# connectors.net
KiCad netlist of a schematic drawn in Altium Designer
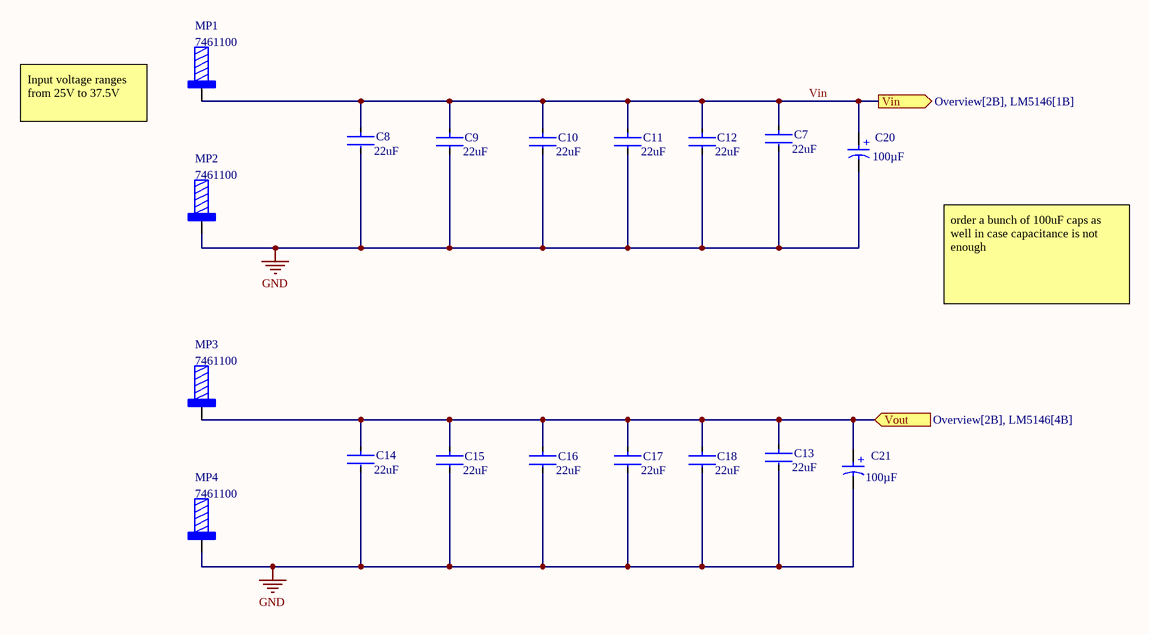
[diagram p0: connectors.SchDoc]

(export (version "E")
  (design (tool "Eeschema 10.0.6"))
  (components
    (comp (ref "C7")
      (value "C2220C226M5R2C7289")
      (footprint "FP-C2220C226M5R2C7289-MFG")
      (description "CAP CER 22UF 50V X7R SMD")
      (fields (field (name "TOLERANCE") "20%") (field (name "CAPACITANCE") "22uF"))
      (libsource (lib "Altium Content Vault") (part "02cd4be3c70576c341d710602a673aa"))
    )
    (comp (ref "C8")
      (value "C2220C226M5R2C7289")
      (footprint "FP-C2220C226M5R2C7289-MFG")
      (description "CAP CER 22UF 50V X7R SMD")
      (fields (field (name "TOLERANCE") "20%") (field (name "CAPACITANCE") "22uF"))
      (libsource (lib "Altium Content Vault") (part "02cd4be3c70576c341d710602a673aa"))
    )
    (comp (ref "C9")
      (value "C2220C226M5R2C7289")
      (footprint "FP-C2220C226M5R2C7289-MFG")
      (description "CAP CER 22UF 50V X7R SMD")
      (fields (field (name "TOLERANCE") "20%") (field (name "CAPACITANCE") "22uF"))
      (libsource (lib "Altium Content Vault") (part "02cd4be3c70576c341d710602a673aa"))
    )
    (comp (ref "C10")
      (value "C2220C226M5R2C7289")
      (footprint "FP-C2220C226M5R2C7289-MFG")
      (description "CAP CER 22UF 50V X7R SMD")
      (fields (field (name "TOLERANCE") "20%") (field (name "CAPACITANCE") "22uF"))
      (libsource (lib "Altium Content Vault") (part "02cd4be3c70576c341d710602a673aa"))
    )
    (comp (ref "C11")
      (value "C2220C226M5R2C7289")
      (footprint "FP-C2220C226M5R2C7289-MFG")
      (description "CAP CER 22UF 50V X7R SMD")
      (fields (field (name "TOLERANCE") "20%") (field (name "CAPACITANCE") "22uF"))
      (libsource (lib "Altium Content Vault") (part "02cd4be3c70576c341d710602a673aa"))
    )
    (comp (ref "C12")
      (value "C2220C226M5R2C7289")
      (footprint "FP-C2220C226M5R2C7289-MFG")
      (description "CAP CER 22UF 50V X7R SMD")
      (fields (field (name "TOLERANCE") "20%") (field (name "CAPACITANCE") "22uF"))
      (libsource (lib "Altium Content Vault") (part "02cd4be3c70576c341d710602a673aa"))
    )
    (comp (ref "C13")
      (value "C2220C226M5R2C7289")
      (footprint "FP-C2220C226M5R2C7289-MFG")
      (description "CAP CER 22UF 50V X7R SMD")
      (fields (field (name "TOLERANCE") "20%") (field (name "CAPACITANCE") "22uF"))
      (libsource (lib "Altium Content Vault") (part "02cd4be3c70576c341d710602a673aa"))
    )
    (comp (ref "C14")
      (value "C2220C226M5R2C7289")
      (footprint "FP-C2220C226M5R2C7289-MFG")
      (description "CAP CER 22UF 50V X7R SMD")
      (fields (field (name "TOLERANCE") "20%") (field (name "CAPACITANCE") "22uF"))
      (libsource (lib "Altium Content Vault") (part "02cd4be3c70576c341d710602a673aa"))
    )
    (comp (ref "C15")
      (value "C2220C226M5R2C7289")
      (footprint "FP-C2220C226M5R2C7289-MFG")
      (description "CAP CER 22UF 50V X7R SMD")
      (fields (field (name "TOLERANCE") "20%") (field (name "CAPACITANCE") "22uF"))
      (libsource (lib "Altium Content Vault") (part "02cd4be3c70576c341d710602a673aa"))
    )
    (comp (ref "C16")
      (value "C2220C226M5R2C7289")
      (footprint "FP-C2220C226M5R2C7289-MFG")
      (description "CAP CER 22UF 50V X7R SMD")
      (fields (field (name "TOLERANCE") "20%") (field (name "CAPACITANCE") "22uF"))
      (libsource (lib "Altium Content Vault") (part "02cd4be3c70576c341d710602a673aa"))
    )
    (comp (ref "C17")
      (value "C2220C226M5R2C7289")
      (footprint "FP-C2220C226M5R2C7289-MFG")
      (description "CAP CER 22UF 50V X7R SMD")
      (fields (field (name "TOLERANCE") "20%") (field (name "CAPACITANCE") "22uF"))
      (libsource (lib "Altium Content Vault") (part "02cd4be3c70576c341d710602a673aa"))
    )
    (comp (ref "C18")
      (value "C2220C226M5R2C7289")
      (footprint "FP-C2220C226M5R2C7289-MFG")
      (description "CAP CER 22UF 50V X7R SMD")
      (fields (field (name "TOLERANCE") "20%") (field (name "CAPACITANCE") "22uF"))
      (libsource (lib "Altium Content Vault") (part "02cd4be3c70576c341d710602a673aa"))
    )
    (comp (ref "C20")
      (value "860040674004")
      (footprint "WCAP-ATUL_D8H11.5")
      (description "WCAP-ATUL Aluminum Electrolytic Capacitors")
      (fields (field (name "TOLERANCE") "20%") (field (name "CAPACITANCE") "100µF"))
      (libsource (lib "Altium Content Vault") (part "Capacitor_Polarized"))
    )
    (comp (ref "C21")
      (value "860040674004")
      (footprint "WCAP-ATUL_D8H11.5")
      (description "WCAP-ATUL Aluminum Electrolytic Capacitors")
      (fields (field (name "TOLERANCE") "20%") (field (name "CAPACITANCE") "100µF"))
      (libsource (lib "Altium Content Vault") (part "Capacitor_Polarized"))
    )
    (comp (ref "MP1")
      (value "7461100")
      (footprint "7461100_chemical surface")
      (description "PCB power element shank terminal, 36P M10")
      (libsource (lib "Altium Content Vault") (part "WP-SHFU"))
    )
    (comp (ref "MP2")
      (value "7461100")
      (footprint "7461100_chemical surface")
      (description "PCB power element shank terminal, 36P M10")
      (libsource (lib "Altium Content Vault") (part "WP-SHFU"))
    )
    (comp (ref "MP3")
      (value "7461100")
      (footprint "7461100_chemical surface")
      (description "PCB power element shank terminal, 36P M10")
      (libsource (lib "Altium Content Vault") (part "WP-SHFU"))
    )
    (comp (ref "MP4")
      (value "7461100")
      (footprint "7461100_chemical surface")
      (description "PCB power element shank terminal, 36P M10")
      (libsource (lib "Altium Content Vault") (part "WP-SHFU"))
    )
  )
  (nets
    (net (code "1") (name "/Vin") (class "Default")
      (node (ref "C10") (pin "1") (pinfunction "1_1") (pintype "passive"))
      (node (ref "C11") (pin "1") (pinfunction "1_1") (pintype "passive"))
      (node (ref "C12") (pin "1") (pinfunction "1_1") (pintype "passive"))
      (node (ref "C20") (pin "1") (pinfunction "P_1") (pintype "passive"))
      (node (ref "C7") (pin "1") (pinfunction "1_1") (pintype "passive"))
      (node (ref "C8") (pin "1") (pinfunction "1_1") (pintype "passive"))
      (node (ref "C9") (pin "1") (pinfunction "1_1") (pintype "passive"))
      (node (ref "MP1") (pin "1") (pinfunction "1_1") (pintype "passive"))
    )
    (net (code "2") (name "/Vout") (class "Default")
      (node (ref "C13") (pin "1") (pinfunction "1_1") (pintype "passive"))
      (node (ref "C14") (pin "1") (pinfunction "1_1") (pintype "passive"))
      (node (ref "C15") (pin "1") (pinfunction "1_1") (pintype "passive"))
      (node (ref "C16") (pin "1") (pinfunction "1_1") (pintype "passive"))
      (node (ref "C17") (pin "1") (pinfunction "1_1") (pintype "passive"))
      (node (ref "C18") (pin "1") (pinfunction "1_1") (pintype "passive"))
      (node (ref "C21") (pin "1") (pinfunction "P_1") (pintype "passive"))
      (node (ref "MP3") (pin "1") (pinfunction "1_1") (pintype "passive"))
    )
    (net (code "3") (name "GND") (class "Default")
      (node (ref "C10") (pin "2") (pinfunction "2_2") (pintype "passive"))
      (node (ref "C11") (pin "2") (pinfunction "2_2") (pintype "passive"))
      (node (ref "C12") (pin "2") (pinfunction "2_2") (pintype "passive"))
      (node (ref "C13") (pin "2") (pinfunction "2_2") (pintype "passive"))
      (node (ref "C14") (pin "2") (pinfunction "2_2") (pintype "passive"))
      (node (ref "C15") (pin "2") (pinfunction "2_2") (pintype "passive"))
      (node (ref "C16") (pin "2") (pinfunction "2_2") (pintype "passive"))
      (node (ref "C17") (pin "2") (pinfunction "2_2") (pintype "passive"))
      (node (ref "C18") (pin "2") (pinfunction "2_2") (pintype "passive"))
      (node (ref "C20") (pin "2") (pinfunction "N_2") (pintype "passive"))
      (node (ref "C21") (pin "2") (pinfunction "N_2") (pintype "passive"))
      (node (ref "C7") (pin "2") (pinfunction "2_2") (pintype "passive"))
      (node (ref "C8") (pin "2") (pinfunction "2_2") (pintype "passive"))
      (node (ref "C9") (pin "2") (pinfunction "2_2") (pintype "passive"))
      (node (ref "MP2") (pin "1") (pinfunction "1_1") (pintype "passive"))
      (node (ref "MP4") (pin "1") (pinfunction "1_1") (pintype "passive"))
    )
  )
)
